# wear_fixture_board.net
KiCad netlist of a schematic drawn in EAGLE
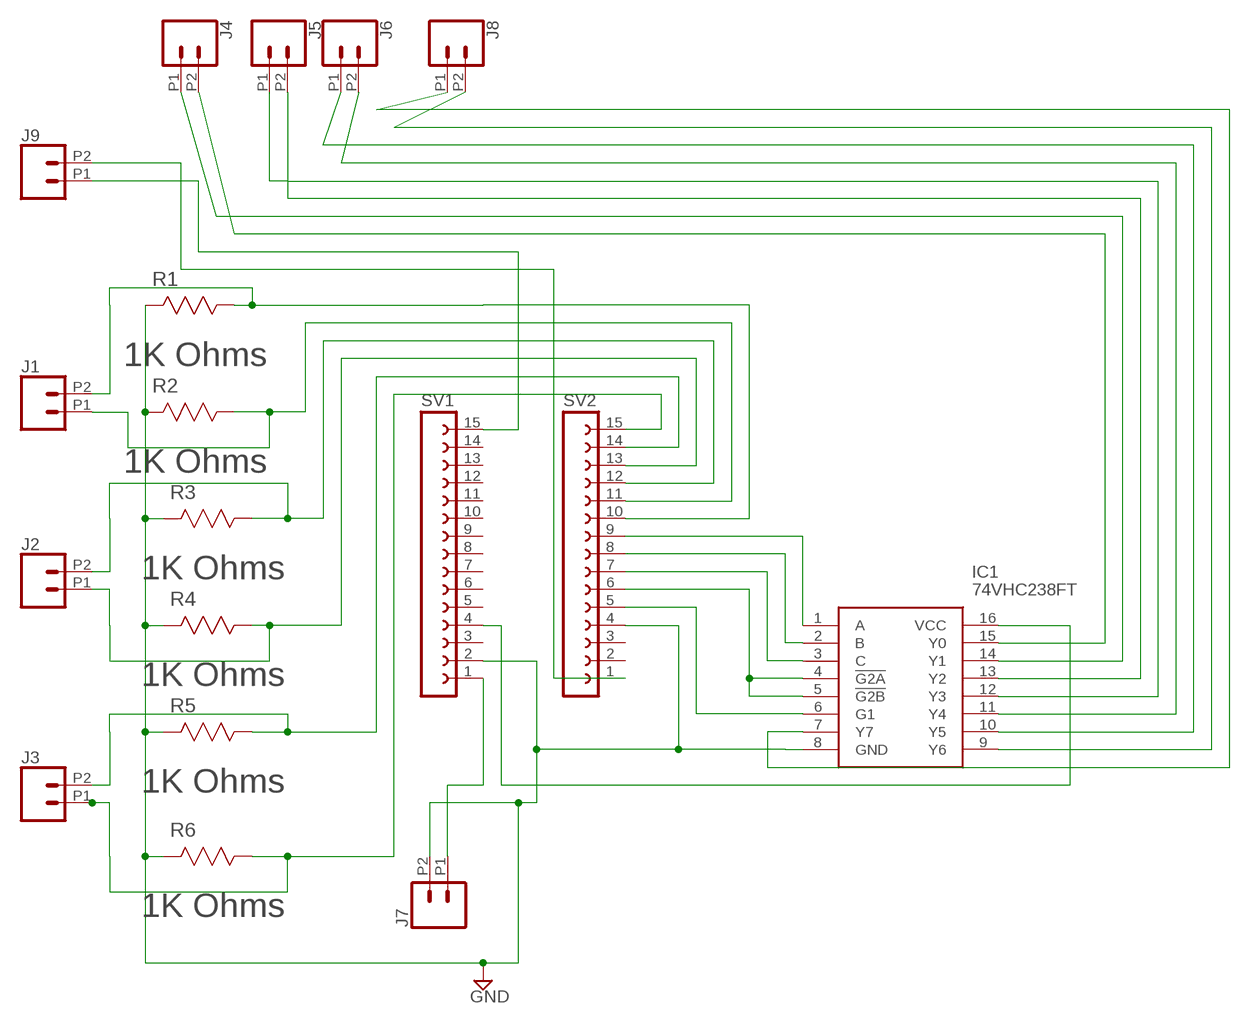
[diagram p0: schematic, sheet 1]

(export (version "E")
  (design (tool "Eeschema 10.0.6"))
  (components
    (comp (ref "IC1")
      (value "74VHC238FT")
      (footprint "eagle-import:SOP65P640X120-16N")
      (fields (field (name "MOUSER_PART_NUMBER") "757-74VHC238FT"))
      (libsource (lib "eagle-import") (part "74VHC238FT"))
    )
    (comp (ref "J1")
      (value "CONN_022.54MM_SCREWTERM")
      (footprint "eagle-import:1X02_2.54_SCREWTERM")
      (libsource (lib "eagle-import") (part "CONN_022.54MM_SCREWTERM"))
    )
    (comp (ref "J2")
      (value "CONN_022.54MM_SCREWTERM")
      (footprint "eagle-import:1X02_2.54_SCREWTERM")
      (libsource (lib "eagle-import") (part "CONN_022.54MM_SCREWTERM"))
    )
    (comp (ref "J3")
      (value "CONN_022.54MM_SCREWTERM")
      (footprint "eagle-import:1X02_2.54_SCREWTERM")
      (libsource (lib "eagle-import") (part "CONN_022.54MM_SCREWTERM"))
    )
    (comp (ref "J4")
      (value "CONN_022.54MM_SCREWTERM")
      (footprint "eagle-import:1X02_2.54_SCREWTERM")
      (libsource (lib "eagle-import") (part "CONN_022.54MM_SCREWTERM"))
    )
    (comp (ref "J5")
      (value "CONN_022.54MM_SCREWTERM")
      (footprint "eagle-import:1X02_2.54_SCREWTERM")
      (libsource (lib "eagle-import") (part "CONN_022.54MM_SCREWTERM"))
    )
    (comp (ref "J6")
      (value "CONN_022.54MM_SCREWTERM")
      (footprint "eagle-import:1X02_2.54_SCREWTERM")
      (libsource (lib "eagle-import") (part "CONN_022.54MM_SCREWTERM"))
    )
    (comp (ref "J7")
      (value "CONN_022.54MM_SCREWTERM")
      (footprint "eagle-import:1X02_2.54_SCREWTERM")
      (libsource (lib "eagle-import") (part "CONN_022.54MM_SCREWTERM"))
    )
    (comp (ref "J8")
      (value "CONN_022.54MM_SCREWTERM")
      (footprint "eagle-import:1X02_2.54_SCREWTERM")
      (libsource (lib "eagle-import") (part "CONN_022.54MM_SCREWTERM"))
    )
    (comp (ref "J9")
      (value "CONN_022.54MM_SCREWTERM")
      (footprint "eagle-import:1X02_2.54_SCREWTERM")
      (libsource (lib "eagle-import") (part "CONN_022.54MM_SCREWTERM"))
    )
    (comp (ref "R1")
      (value "1K Ohms")
      (footprint "eagle-import:RESC3216X71N")
      (fields (field (name "MPN") "CRCW12061K00FKEA") (field (name "TOLERANCE") "±1%"))
      (libsource (lib "eagle-import") (part "CRCW12061K00FKEA"))
    )
    (comp (ref "R2")
      (value "1K Ohms")
      (footprint "eagle-import:RESC3216X71N")
      (fields (field (name "MPN") "CRCW12061K00FKEA") (field (name "TOLERANCE") "±1%"))
      (libsource (lib "eagle-import") (part "CRCW12061K00FKEA"))
    )
    (comp (ref "R3")
      (value "1K Ohms")
      (footprint "eagle-import:RESC3216X71N")
      (fields (field (name "MPN") "CRCW12061K00FKEA") (field (name "TOLERANCE") "±1%"))
      (libsource (lib "eagle-import") (part "CRCW12061K00FKEA"))
    )
    (comp (ref "R4")
      (value "1K Ohms")
      (footprint "eagle-import:RESC3216X71N")
      (fields (field (name "MPN") "CRCW12061K00FKEA") (field (name "TOLERANCE") "±1%"))
      (libsource (lib "eagle-import") (part "CRCW12061K00FKEA"))
    )
    (comp (ref "R5")
      (value "1K Ohms")
      (footprint "eagle-import:RESC3216X71N")
      (fields (field (name "MPN") "CRCW12061K00FKEA") (field (name "TOLERANCE") "±1%"))
      (libsource (lib "eagle-import") (part "CRCW12061K00FKEA"))
    )
    (comp (ref "R6")
      (value "1K Ohms")
      (footprint "eagle-import:RESC3216X71N")
      (fields (field (name "MPN") "CRCW12061K00FKEA") (field (name "TOLERANCE") "±1%"))
      (libsource (lib "eagle-import") (part "CRCW12061K00FKEA"))
    )
    (comp (ref "SV1")
      (value "FE15-1")
      (footprint "eagle-import:FE15")
      (libsource (lib "eagle-import") (part "FE15-1"))
    )
    (comp (ref "SV2")
      (value "FE15-1")
      (footprint "eagle-import:FE15")
      (libsource (lib "eagle-import") (part "FE15-1"))
    )
  )
  (nets
    (net (code "1") (name "GND") (class "Default")
      (node (ref "IC1") (pin "8") (pinfunction "GND_8") (pintype "power_in"))
      (node (ref "J7") (pin "P2") (pinfunction "2_P2") (pintype "passive"))
      (node (ref "R1") (pin "2") (pinfunction "2_2") (pintype "passive"))
      (node (ref "R2") (pin "2") (pinfunction "2_2") (pintype "passive"))
      (node (ref "R3") (pin "2") (pinfunction "2_2") (pintype "passive"))
      (node (ref "R4") (pin "2") (pinfunction "2_2") (pintype "passive"))
      (node (ref "R5") (pin "2") (pinfunction "2_2") (pintype "passive"))
      (node (ref "R6") (pin "2") (pinfunction "2_2") (pintype "passive"))
      (node (ref "SV1") (pin "2") (pinfunction "2_2") (pintype "passive"))
      (node (ref "SV2") (pin "4") (pinfunction "4_4") (pintype "passive"))
    )
    (net (code "2") (name "Net-(IC1-A)") (class "Default")
      (node (ref "IC1") (pin "1") (pinfunction "A_1") (pintype "input"))
      (node (ref "SV2") (pin "9") (pinfunction "9_9") (pintype "passive"))
    )
    (net (code "3") (name "Net-(IC1-B)") (class "Default")
      (node (ref "IC1") (pin "2") (pinfunction "B_2") (pintype "input"))
      (node (ref "SV2") (pin "8") (pinfunction "8_8") (pintype "passive"))
    )
    (net (code "4") (name "Net-(IC1-C)") (class "Default")
      (node (ref "IC1") (pin "3") (pinfunction "C_3") (pintype "input"))
      (node (ref "SV2") (pin "7") (pinfunction "7_7") (pintype "passive"))
    )
    (net (code "5") (name "Net-(IC1-G1)") (class "Default")
      (node (ref "IC1") (pin "6") (pinfunction "G1_6") (pintype "input"))
      (node (ref "SV2") (pin "5") (pinfunction "5_5") (pintype "passive"))
    )
    (net (code "6") (name "Net-(IC1-VCC)") (class "Default")
      (node (ref "IC1") (pin "16") (pinfunction "VCC_16") (pintype "power_in"))
      (node (ref "SV1") (pin "4") (pinfunction "4_4") (pintype "passive"))
    )
    (net (code "7") (name "Net-(IC1-Y0)") (class "Default")
      (node (ref "IC1") (pin "15") (pinfunction "Y0_15") (pintype "output"))
      (node (ref "J4") (pin "P2") (pinfunction "2_P2") (pintype "passive"))
    )
    (net (code "8") (name "Net-(IC1-Y1)") (class "Default")
      (node (ref "IC1") (pin "14") (pinfunction "Y1_14") (pintype "output"))
      (node (ref "J4") (pin "P1") (pinfunction "1_P1") (pintype "passive"))
    )
    (net (code "9") (name "Net-(IC1-Y2)") (class "Default")
      (node (ref "IC1") (pin "13") (pinfunction "Y2_13") (pintype "output"))
      (node (ref "J5") (pin "P2") (pinfunction "2_P2") (pintype "passive"))
    )
    (net (code "10") (name "Net-(IC1-Y3)") (class "Default")
      (node (ref "IC1") (pin "12") (pinfunction "Y3_12") (pintype "output"))
      (node (ref "J5") (pin "P1") (pinfunction "1_P1") (pintype "passive"))
    )
    (net (code "11") (name "Net-(IC1-Y4)") (class "Default")
      (node (ref "IC1") (pin "11") (pinfunction "Y4_11") (pintype "output"))
      (node (ref "J6") (pin "P2") (pinfunction "2_P2") (pintype "passive"))
    )
    (net (code "12") (name "Net-(IC1-Y5)") (class "Default")
      (node (ref "IC1") (pin "10") (pinfunction "Y5_10") (pintype "output"))
      (node (ref "J6") (pin "P1") (pinfunction "1_P1") (pintype "passive"))
    )
    (net (code "13") (name "Net-(IC1-Y6)") (class "Default")
      (node (ref "IC1") (pin "9") (pinfunction "Y6_9") (pintype "output"))
      (node (ref "J8") (pin "P2") (pinfunction "2_P2") (pintype "passive"))
    )
    (net (code "14") (name "Net-(IC1-Y7)") (class "Default")
      (node (ref "IC1") (pin "7") (pinfunction "Y7_7") (pintype "output"))
      (node (ref "J8") (pin "P1") (pinfunction "1_P1") (pintype "passive"))
    )
    (net (code "15") (name "Net-(IC1-~{G2A})") (class "Default")
      (node (ref "IC1") (pin "4") (pinfunction "~{G2A}_4") (pintype "input"))
      (node (ref "IC1") (pin "5") (pinfunction "~{G2B}_5") (pintype "input"))
      (node (ref "SV2") (pin "6") (pinfunction "6_6") (pintype "passive"))
    )
    (net (code "16") (name "Net-(J1-1)") (class "Default")
      (node (ref "J1") (pin "P1") (pinfunction "1_P1") (pintype "passive"))
      (node (ref "R2") (pin "1") (pinfunction "1_1") (pintype "passive"))
      (node (ref "SV2") (pin "11") (pinfunction "11_11") (pintype "passive"))
    )
    (net (code "17") (name "Net-(J1-2)") (class "Default")
      (node (ref "J1") (pin "P2") (pinfunction "2_P2") (pintype "passive"))
      (node (ref "R1") (pin "1") (pinfunction "1_1") (pintype "passive"))
      (node (ref "SV2") (pin "10") (pinfunction "10_10") (pintype "passive"))
    )
    (net (code "18") (name "Net-(J2-1)") (class "Default")
      (node (ref "J2") (pin "P1") (pinfunction "1_P1") (pintype "passive"))
      (node (ref "R4") (pin "1") (pinfunction "1_1") (pintype "passive"))
      (node (ref "SV2") (pin "13") (pinfunction "13_13") (pintype "passive"))
    )
    (net (code "19") (name "Net-(J2-2)") (class "Default")
      (node (ref "J2") (pin "P2") (pinfunction "2_P2") (pintype "passive"))
      (node (ref "R3") (pin "1") (pinfunction "1_1") (pintype "passive"))
      (node (ref "SV2") (pin "12") (pinfunction "12_12") (pintype "passive"))
    )
    (net (code "20") (name "Net-(J3-1)") (class "Default")
      (node (ref "J3") (pin "P1") (pinfunction "1_P1") (pintype "passive"))
      (node (ref "R6") (pin "1") (pinfunction "1_1") (pintype "passive"))
      (node (ref "SV2") (pin "15") (pinfunction "15_15") (pintype "passive"))
    )
    (net (code "21") (name "Net-(J3-2)") (class "Default")
      (node (ref "J3") (pin "P2") (pinfunction "2_P2") (pintype "passive"))
      (node (ref "R5") (pin "1") (pinfunction "1_1") (pintype "passive"))
      (node (ref "SV2") (pin "14") (pinfunction "14_14") (pintype "passive"))
    )
    (net (code "22") (name "Net-(J7-1)") (class "Default")
      (node (ref "J7") (pin "P1") (pinfunction "1_P1") (pintype "passive"))
      (node (ref "SV1") (pin "1") (pinfunction "1_1") (pintype "passive"))
    )
    (net (code "23") (name "Net-(J9-1)") (class "Default")
      (node (ref "J9") (pin "P1") (pinfunction "1_P1") (pintype "passive"))
      (node (ref "SV1") (pin "15") (pinfunction "15_15") (pintype "passive"))
    )
    (net (code "24") (name "Net-(J9-2)") (class "Default")
      (node (ref "J9") (pin "P2") (pinfunction "2_P2") (pintype "passive"))
      (node (ref "SV2") (pin "1") (pinfunction "1_1") (pintype "passive"))
    )
    (net (code "25") (name "unconnected-(SV1-Pad3)") (class "Default")
      (node (ref "SV1") (pin "3") (pinfunction "3_3") (pintype "passive"))
    )
    (net (code "26") (name "unconnected-(SV1-Pad5)") (class "Default")
      (node (ref "SV1") (pin "5") (pinfunction "5_5") (pintype "passive"))
    )
    (net (code "27") (name "unconnected-(SV1-Pad6)") (class "Default")
      (node (ref "SV1") (pin "6") (pinfunction "6_6") (pintype "passive"))
    )
    (net (code "28") (name "unconnected-(SV1-Pad7)") (class "Default")
      (node (ref "SV1") (pin "7") (pinfunction "7_7") (pintype "passive"))
    )
    (net (code "29") (name "unconnected-(SV1-Pad8)") (class "Default")
      (node (ref "SV1") (pin "8") (pinfunction "8_8") (pintype "passive"))
    )
    (net (code "30") (name "unconnected-(SV1-Pad9)") (class "Default")
      (node (ref "SV1") (pin "9") (pinfunction "9_9") (pintype "passive"))
    )
    (net (code "31") (name "unconnected-(SV1-Pad10)") (class "Default")
      (node (ref "SV1") (pin "10") (pinfunction "10_10") (pintype "passive"))
    )
    (net (code "32") (name "unconnected-(SV1-Pad11)") (class "Default")
      (node (ref "SV1") (pin "11") (pinfunction "11_11") (pintype "passive"))
    )
    (net (code "33") (name "unconnected-(SV1-Pad12)") (class "Default")
      (node (ref "SV1") (pin "12") (pinfunction "12_12") (pintype "passive"))
    )
    (net (code "34") (name "unconnected-(SV1-Pad13)") (class "Default")
      (node (ref "SV1") (pin "13") (pinfunction "13_13") (pintype "passive"))
    )
    (net (code "35") (name "unconnected-(SV1-Pad14)") (class "Default")
      (node (ref "SV1") (pin "14") (pinfunction "14_14") (pintype "passive"))
    )
    (net (code "36") (name "unconnected-(SV2-Pad2)") (class "Default")
      (node (ref "SV2") (pin "2") (pinfunction "2_2") (pintype "passive"))
    )
    (net (code "37") (name "unconnected-(SV2-Pad3)") (class "Default")
      (node (ref "SV2") (pin "3") (pinfunction "3_3") (pintype "passive"))
    )
  )
)
